# Connectors.net
KiCad netlist of a schematic drawn in Altium Designer
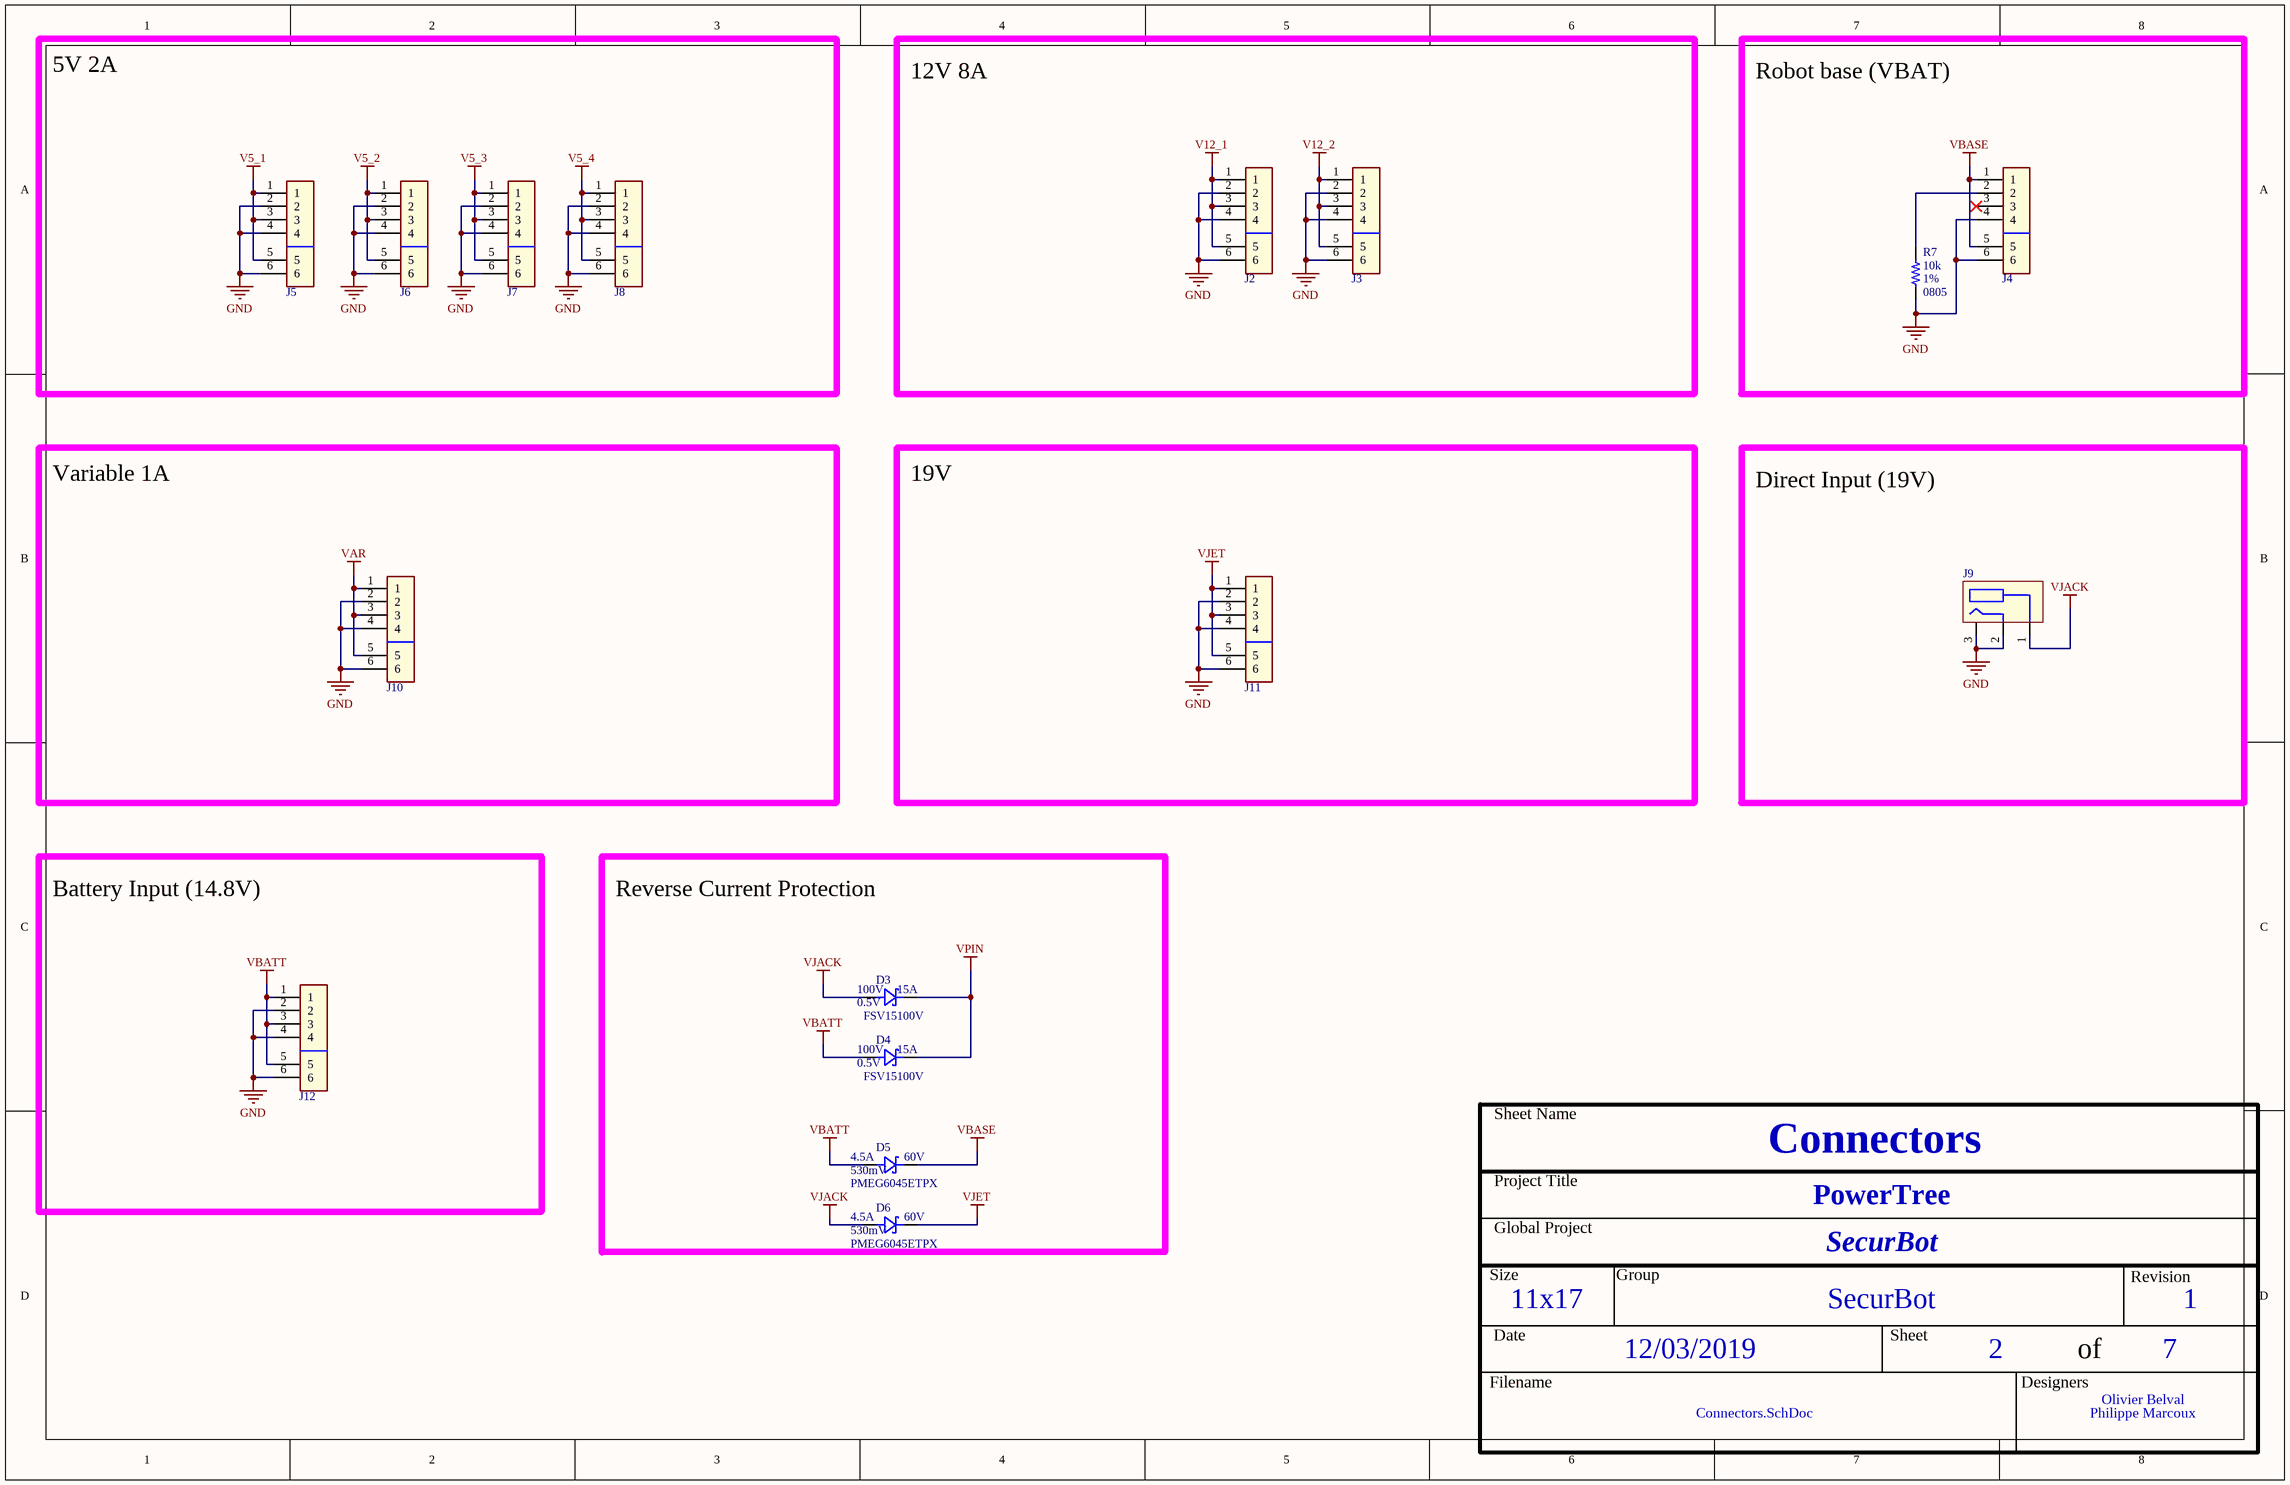
[diagram p0: Connectors.SchDoc]

(export (version "E")
  (design (tool "Eeschema 10.0.6"))
  (components
    (comp (ref "D3")
      (value "DIODE_SCH_FSV15100V")
      (footprint "TO277-3")
      (description "Diode Schottky 60V 4.5A Surface Mount CFP5")
      (fields
        (field (name "VOLTAGE") "100V")
        (field (name "CURRENT") "15A")
        (field (name "VF") "0.5V")
        (field (name "PART NUMBER") "FSV15100V")
      )
      (libsource (lib "SecureBot") (part "DIODE_SCH_FSV15100V"))
    )
    (comp (ref "D4")
      (value "DIODE_SCH_FSV15100V")
      (footprint "TO277-3")
      (description "Diode Schottky 60V 4.5A Surface Mount CFP5")
      (fields
        (field (name "VOLTAGE") "100V")
        (field (name "CURRENT") "15A")
        (field (name "VF") "0.5V")
        (field (name "PART NUMBER") "FSV15100V")
      )
      (libsource (lib "SecureBot") (part "DIODE_SCH_FSV15100V"))
    )
    (comp (ref "D5")
      (value "DIODE_SCH_PMEG6045ETPX")
      (footprint "DO-214AC_SOD128")
      (description "Diode Schottky 60V 4.5A Surface Mount CFP5")
      (fields
        (field (name "VOLTAGE") "60V")
        (field (name "CURRENT") "4.5A")
        (field (name "VF") "530mV")
        (field (name "PART NUMBER") "PMEG6045ETPX")
      )
      (libsource (lib "SecureBot") (part "DIODE_SCH_PMEG6045ETPX"))
    )
    (comp (ref "D6")
      (value "DIODE_SCH_PMEG6045ETPX")
      (footprint "DO-214AC_SOD128")
      (description "Diode Schottky 60V 4.5A Surface Mount CFP5")
      (fields
        (field (name "VOLTAGE") "60V")
        (field (name "CURRENT") "4.5A")
        (field (name "VF") "530mV")
        (field (name "PART NUMBER") "PMEG6045ETPX")
      )
      (libsource (lib "SecureBot") (part "DIODE_SCH_PMEG6045ETPX"))
    )
    (comp (ref "J2")
      (value "MOLEX 4 POS - TERMINAL BLOCK 2 POS")
      (footprint "MOLEX4POS_TERMBLOCK2POS")
      (fields (field (name "PART NUMBER") "0039281043") (field (name "PART NUMBER_1") "OSTOQ023250"))
      (libsource (lib "SecureBot") (part "MOLEX 4 POS - TERMINAL BLOCK 2 POS"))
    )
    (comp (ref "J3")
      (value "MOLEX 4 POS - TERMINAL BLOCK 2 POS")
      (footprint "MOLEX4POS_TERMBLOCK2POS")
      (fields (field (name "PART NUMBER") "0039281043") (field (name "PART NUMBER_1") "OSTOQ023250"))
      (libsource (lib "SecureBot") (part "MOLEX 4 POS - TERMINAL BLOCK 2 POS"))
    )
    (comp (ref "J4")
      (value "MOLEX 4 POS - TERMINAL BLOCK 2 POS")
      (footprint "MOLEX4POS_TERMBLOCK2POS")
      (fields (field (name "PART NUMBER") "0039281043") (field (name "PART NUMBER_1") "OSTOQ023250"))
      (libsource (lib "SecureBot") (part "MOLEX 4 POS - TERMINAL BLOCK 2 POS"))
    )
    (comp (ref "J5")
      (value "MOLEX 4 POS - TERMINAL BLOCK 2 POS")
      (footprint "MOLEX4POS_TERMBLOCK2POS")
      (fields (field (name "PART NUMBER") "0039281043") (field (name "PART NUMBER_1") "OSTOQ023250"))
      (libsource (lib "SecureBot") (part "MOLEX 4 POS - TERMINAL BLOCK 2 POS"))
    )
    (comp (ref "J6")
      (value "MOLEX 4 POS - TERMINAL BLOCK 2 POS")
      (footprint "MOLEX4POS_TERMBLOCK2POS")
      (fields (field (name "PART NUMBER") "0039281043") (field (name "PART NUMBER_1") "OSTOQ023250"))
      (libsource (lib "SecureBot") (part "MOLEX 4 POS - TERMINAL BLOCK 2 POS"))
    )
    (comp (ref "J7")
      (value "MOLEX 4 POS - TERMINAL BLOCK 2 POS")
      (footprint "MOLEX4POS_TERMBLOCK2POS")
      (fields (field (name "PART NUMBER") "0039281043") (field (name "PART NUMBER_1") "OSTOQ023250"))
      (libsource (lib "SecureBot") (part "MOLEX 4 POS - TERMINAL BLOCK 2 POS"))
    )
    (comp (ref "J8")
      (value "MOLEX 4 POS - TERMINAL BLOCK 2 POS")
      (footprint "MOLEX4POS_TERMBLOCK2POS")
      (fields (field (name "PART NUMBER") "0039281043") (field (name "PART NUMBER_1") "OSTOQ023250"))
      (libsource (lib "SecureBot") (part "MOLEX 4 POS - TERMINAL BLOCK 2 POS"))
    )
    (comp (ref "J9")
      (value "Barrel 5.5x2.5mm")
      (footprint "Barrel 5.5mm 2.5mm")
      (description "Jack 5.5x2.5mm")
      (fields (field (name "PART NUMBER") "PJ-082BH"))
      (libsource (lib "SecureBot") (part "Barrel 5.5x2.5mm"))
    )
    (comp (ref "J10")
      (value "MOLEX 4 POS - TERMINAL BLOCK 2 POS")
      (footprint "MOLEX4POS_TERMBLOCK2POS")
      (fields (field (name "PART NUMBER") "0039281043") (field (name "PART NUMBER_1") "OSTOQ023250"))
      (libsource (lib "SecureBot") (part "MOLEX 4 POS - TERMINAL BLOCK 2 POS"))
    )
    (comp (ref "J11")
      (value "MOLEX 4 POS - TERMINAL BLOCK 2 POS")
      (footprint "MOLEX4POS_TERMBLOCK2POS")
      (fields (field (name "PART NUMBER") "0039281043") (field (name "PART NUMBER_1") "OSTOQ023250"))
      (libsource (lib "SecureBot") (part "MOLEX 4 POS - TERMINAL BLOCK 2 POS"))
    )
    (comp (ref "J12")
      (value "MOLEX 4 POS - TERMINAL BLOCK 2 POS")
      (footprint "MOLEX4POS_TERMBLOCK2POS")
      (fields (field (name "PART NUMBER") "0039281043") (field (name "PART NUMBER_1") "OSTOQ023250"))
      (libsource (lib "SecureBot") (part "MOLEX 4 POS - TERMINAL BLOCK 2 POS"))
    )
    (comp (ref "R7")
      (value "10k")
      (footprint "FER_0805")
      (description "RES - 0805")
      (fields
        (field (name "TOLERANCE") "1%")
        (field (name "PACKAGE") "0805")
        (field (name "PART NUMBER") "RMCF0805FT10K0")
      )
      (libsource (lib "SecureBot") (part "RES - 0805"))
    )
  )
  (nets
    (net (code "1") (name "GND") (class "Default")
      (node (ref "J10") (pin "2") (pinfunction "2_2") (pintype "passive"))
      (node (ref "J10") (pin "4") (pinfunction "4_4") (pintype "passive"))
      (node (ref "J10") (pin "6") (pinfunction "6_6") (pintype "passive"))
      (node (ref "J11") (pin "2") (pinfunction "2_2") (pintype "passive"))
      (node (ref "J11") (pin "4") (pinfunction "4_4") (pintype "passive"))
      (node (ref "J11") (pin "6") (pinfunction "6_6") (pintype "passive"))
      (node (ref "J12") (pin "2") (pinfunction "2_2") (pintype "passive"))
      (node (ref "J12") (pin "4") (pinfunction "4_4") (pintype "passive"))
      (node (ref "J12") (pin "6") (pinfunction "6_6") (pintype "passive"))
      (node (ref "J2") (pin "2") (pinfunction "2_2") (pintype "passive"))
      (node (ref "J2") (pin "4") (pinfunction "4_4") (pintype "passive"))
      (node (ref "J2") (pin "6") (pinfunction "6_6") (pintype "passive"))
      (node (ref "J3") (pin "2") (pinfunction "2_2") (pintype "passive"))
      (node (ref "J3") (pin "4") (pinfunction "4_4") (pintype "passive"))
      (node (ref "J3") (pin "6") (pinfunction "6_6") (pintype "passive"))
      (node (ref "J4") (pin "4") (pinfunction "4_4") (pintype "passive"))
      (node (ref "J4") (pin "6") (pinfunction "6_6") (pintype "passive"))
      (node (ref "J5") (pin "2") (pinfunction "2_2") (pintype "passive"))
      (node (ref "J5") (pin "4") (pinfunction "4_4") (pintype "passive"))
      (node (ref "J5") (pin "6") (pinfunction "6_6") (pintype "passive"))
      (node (ref "J6") (pin "2") (pinfunction "2_2") (pintype "passive"))
      (node (ref "J6") (pin "4") (pinfunction "4_4") (pintype "passive"))
      (node (ref "J6") (pin "6") (pinfunction "6_6") (pintype "passive"))
      (node (ref "J7") (pin "2") (pinfunction "2_2") (pintype "passive"))
      (node (ref "J7") (pin "4") (pinfunction "4_4") (pintype "passive"))
      (node (ref "J7") (pin "6") (pinfunction "6_6") (pintype "passive"))
      (node (ref "J8") (pin "2") (pinfunction "2_2") (pintype "passive"))
      (node (ref "J8") (pin "4") (pinfunction "4_4") (pintype "passive"))
      (node (ref "J8") (pin "6") (pinfunction "6_6") (pintype "passive"))
      (node (ref "J9") (pin "2") (pinfunction "2_2") (pintype "passive"))
      (node (ref "J9") (pin "3") (pinfunction "3_3") (pintype "passive"))
      (node (ref "R7") (pin "2") (pinfunction "2_2") (pintype "passive"))
    )
    (net (code "2") (name "Net-(J4-Pad2)") (class "Default")
      (node (ref "J4") (pin "2") (pinfunction "2_2") (pintype "passive"))
      (node (ref "R7") (pin "1") (pinfunction "1_1") (pintype "passive"))
    )
    (net (code "3") (name "V5_1") (class "Default")
      (node (ref "J5") (pin "1") (pinfunction "1_1") (pintype "passive"))
      (node (ref "J5") (pin "3") (pinfunction "3_3") (pintype "passive"))
      (node (ref "J5") (pin "5") (pinfunction "5_5") (pintype "passive"))
    )
    (net (code "4") (name "V5_2") (class "Default")
      (node (ref "J6") (pin "1") (pinfunction "1_1") (pintype "passive"))
      (node (ref "J6") (pin "3") (pinfunction "3_3") (pintype "passive"))
      (node (ref "J6") (pin "5") (pinfunction "5_5") (pintype "passive"))
    )
    (net (code "5") (name "V5_3") (class "Default")
      (node (ref "J7") (pin "1") (pinfunction "1_1") (pintype "passive"))
      (node (ref "J7") (pin "3") (pinfunction "3_3") (pintype "passive"))
      (node (ref "J7") (pin "5") (pinfunction "5_5") (pintype "passive"))
    )
    (net (code "6") (name "V5_4") (class "Default")
      (node (ref "J8") (pin "1") (pinfunction "1_1") (pintype "passive"))
      (node (ref "J8") (pin "3") (pinfunction "3_3") (pintype "passive"))
      (node (ref "J8") (pin "5") (pinfunction "5_5") (pintype "passive"))
    )
    (net (code "7") (name "V12_1") (class "Default")
      (node (ref "J2") (pin "1") (pinfunction "1_1") (pintype "passive"))
      (node (ref "J2") (pin "3") (pinfunction "3_3") (pintype "passive"))
      (node (ref "J2") (pin "5") (pinfunction "5_5") (pintype "passive"))
    )
    (net (code "8") (name "V12_2") (class "Default")
      (node (ref "J3") (pin "1") (pinfunction "1_1") (pintype "passive"))
      (node (ref "J3") (pin "3") (pinfunction "3_3") (pintype "passive"))
      (node (ref "J3") (pin "5") (pinfunction "5_5") (pintype "passive"))
    )
    (net (code "9") (name "VAR") (class "Default")
      (node (ref "J10") (pin "1") (pinfunction "1_1") (pintype "passive"))
      (node (ref "J10") (pin "3") (pinfunction "3_3") (pintype "passive"))
      (node (ref "J10") (pin "5") (pinfunction "5_5") (pintype "passive"))
    )
    (net (code "10") (name "VBASE") (class "Default")
      (node (ref "D5") (pin "2") (pinfunction "2_2") (pintype "passive"))
      (node (ref "J4") (pin "1") (pinfunction "1_1") (pintype "passive"))
      (node (ref "J4") (pin "5") (pinfunction "5_5") (pintype "passive"))
    )
    (net (code "11") (name "VBATT") (class "Default")
      (node (ref "D4") (pin "1") (pinfunction "1_1") (pintype "passive"))
      (node (ref "D5") (pin "1") (pinfunction "1_1") (pintype "passive"))
      (node (ref "J12") (pin "1") (pinfunction "1_1") (pintype "passive"))
      (node (ref "J12") (pin "3") (pinfunction "3_3") (pintype "passive"))
      (node (ref "J12") (pin "5") (pinfunction "5_5") (pintype "passive"))
    )
    (net (code "12") (name "VJACK") (class "Default")
      (node (ref "D3") (pin "1") (pinfunction "1_1") (pintype "passive"))
      (node (ref "D6") (pin "1") (pinfunction "1_1") (pintype "passive"))
      (node (ref "J9") (pin "1") (pinfunction "1_1") (pintype "passive"))
    )
    (net (code "13") (name "VJET") (class "Default")
      (node (ref "D6") (pin "2") (pinfunction "2_2") (pintype "passive"))
      (node (ref "J11") (pin "1") (pinfunction "1_1") (pintype "passive"))
      (node (ref "J11") (pin "3") (pinfunction "3_3") (pintype "passive"))
      (node (ref "J11") (pin "5") (pinfunction "5_5") (pintype "passive"))
    )
    (net (code "14") (name "VPIN") (class "Default")
      (node (ref "D3") (pin "2") (pinfunction "2_2") (pintype "passive"))
      (node (ref "D4") (pin "2") (pinfunction "2_2") (pintype "passive"))
    )
    (net (code "15") (name "unconnected-(J4-Pad3)") (class "Default")
      (node (ref "J4") (pin "3") (pinfunction "3_3") (pintype "passive+no_connect"))
    )
  )
)
